# M5_Access_Switch_Dual_Input.net
KiCad netlist of a schematic drawn in EAGLE
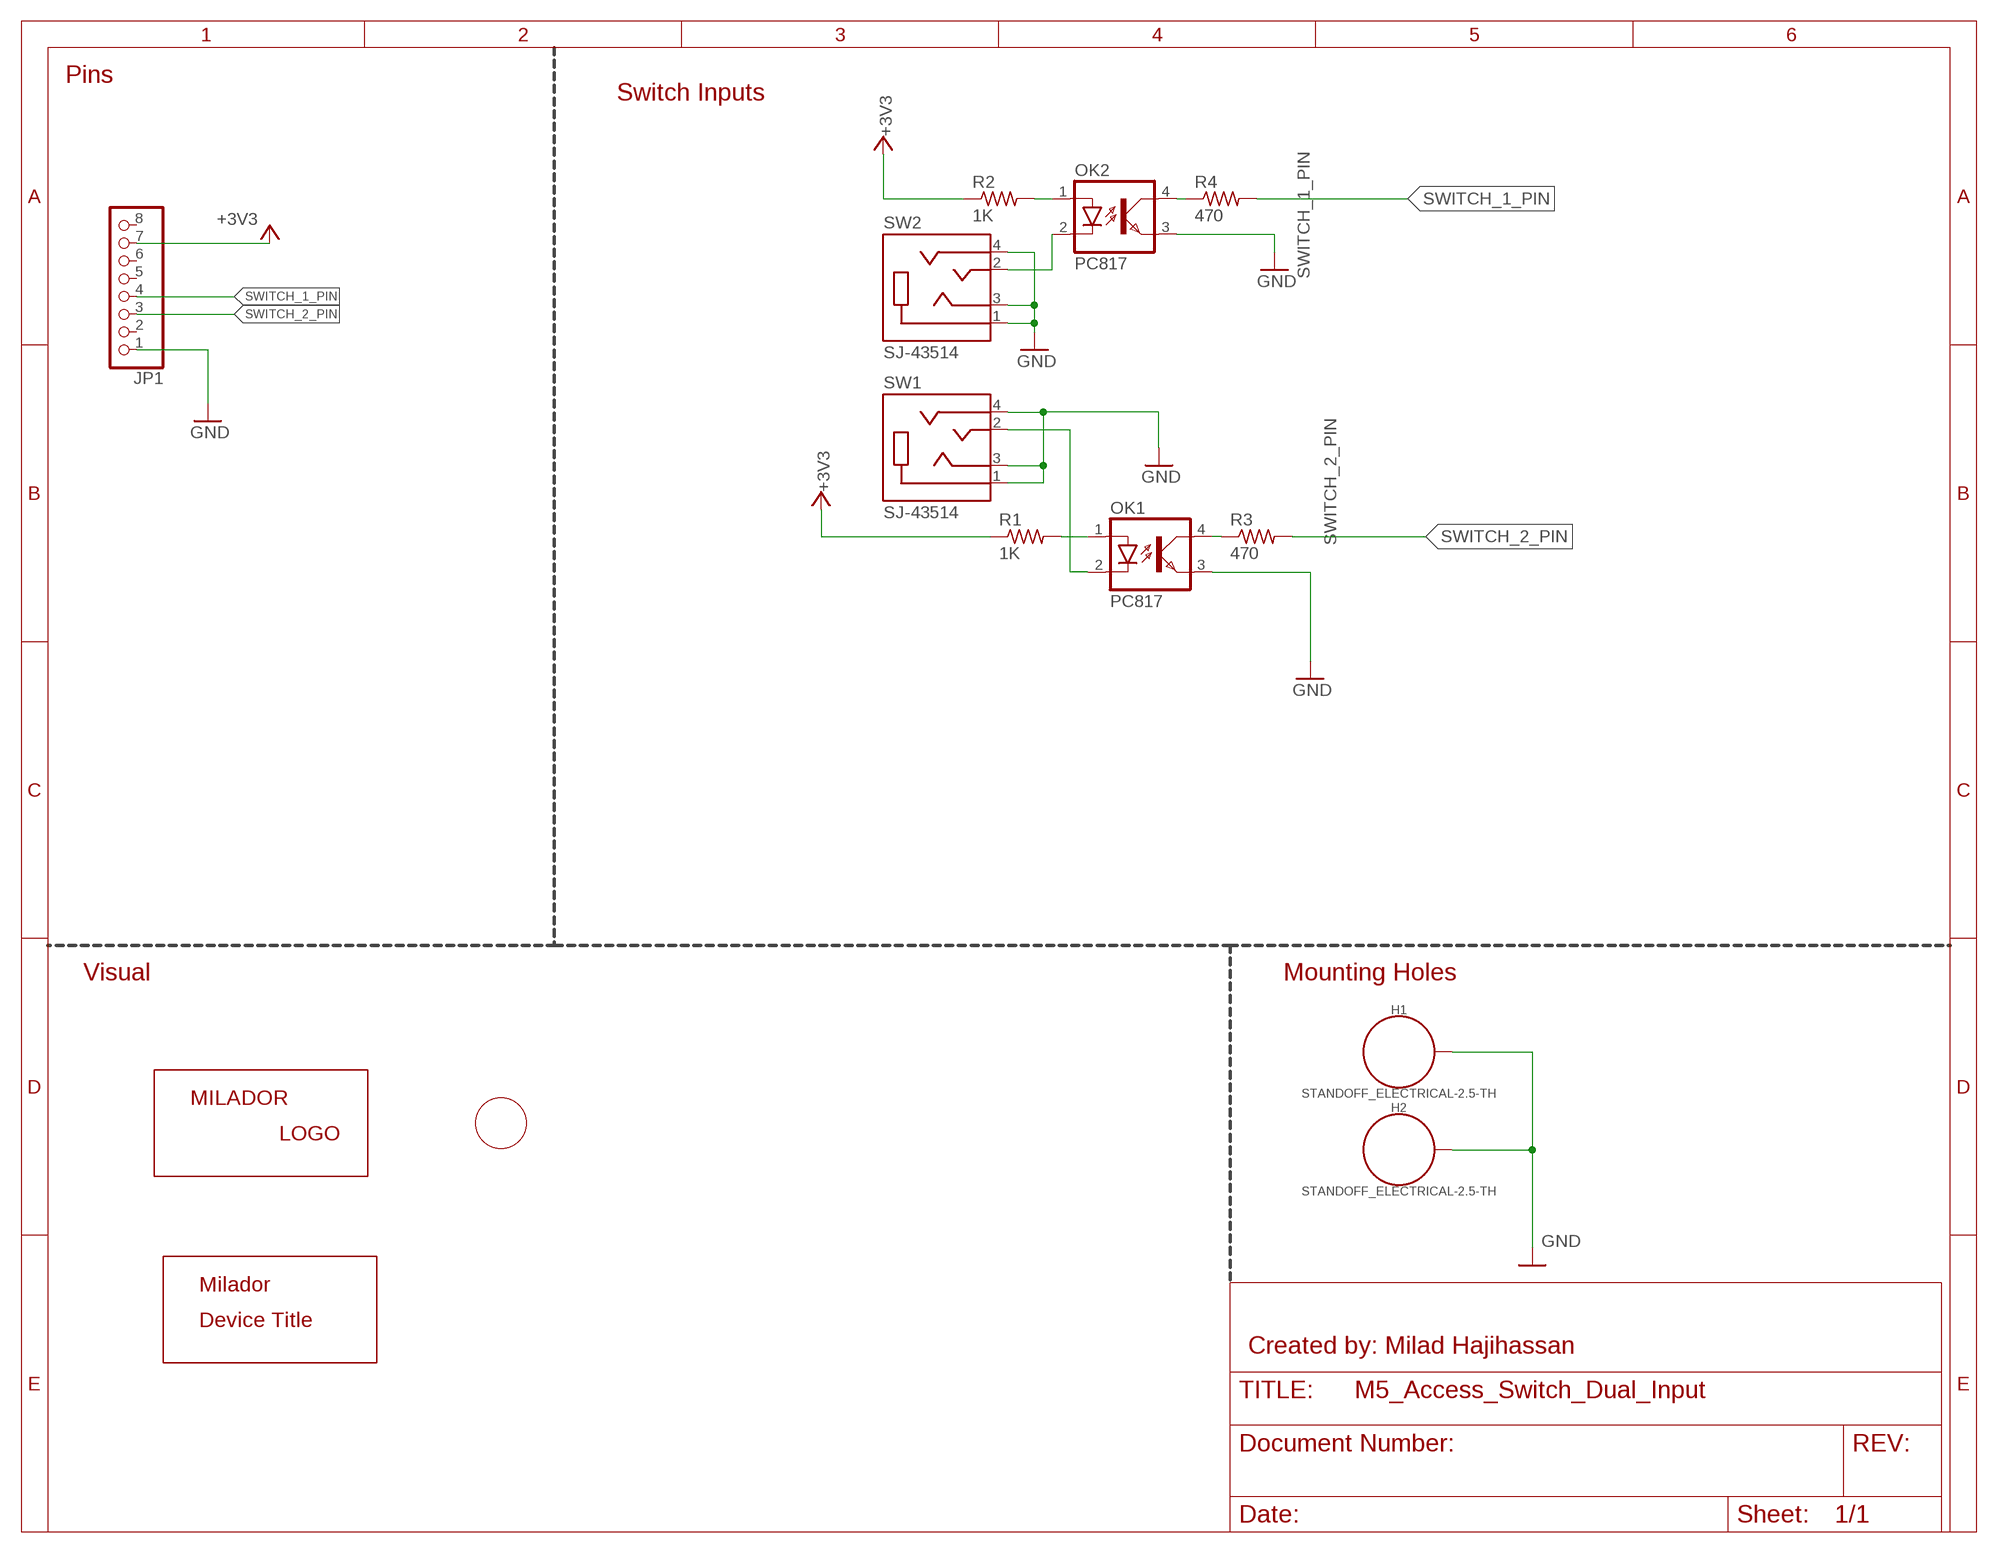
[diagram p0: schematic, sheet 1]

(export (version "E")
  (design (tool "Eeschema 10.0.6"))
  (components
    (comp (ref "H1")
      (value "STANDOFF_ELECTRICAL-2.5-TH")
      (footprint "eagle-import:STANDOFF-ELECTRICAL-2.5-TH")
      (libsource (lib "eagle-import") (part "STANDOFF_ELECTRICAL-2.5-TH"))
    )
    (comp (ref "H2")
      (value "STANDOFF_ELECTRICAL-2.5-TH")
      (footprint "eagle-import:STANDOFF-ELECTRICAL-2.5-TH")
      (libsource (lib "eagle-import") (part "STANDOFF_ELECTRICAL-2.5-TH"))
    )
    (comp (ref "JP1")
      (value "HEADER_MALE-1X8ROUND-RA")
      (footprint "eagle-import:1X08_ROUND_RA")
      (libsource (lib "eagle-import") (part "HEADER_MALE-1X8ROUND-RA"))
    )
    (comp (ref "LABEL_DEVICE_TOP")
      (value "MILADOR-DEVICE-M5-ACCESS-SWITCH")
      (footprint "eagle-import:MILADOR_M5_ACCESS_SWITCH")
      (libsource (lib "eagle-import") (part "MILADOR-DEVICE-M5-ACCESS-SWITCH"))
    )
    (comp (ref "LABEL_INPUT_TOP")
      (value "MILADOR-SWITCH-NAME-SW-INPUT")
      (footprint "eagle-import:SWITCH-INPUT")
      (libsource (lib "eagle-import") (part "MILADOR-SWITCH-NAME-SW-INPUT"))
    )
    (comp (ref "LABEL_LOGO_TOP")
      (value "MILADOR-LOGO-SM")
      (footprint "eagle-import:MILADOR_LOGO2")
      (libsource (lib "eagle-import") (part "MILADOR-LOGO-SM"))
    )
    (comp (ref "OK1")
      (value "PC817")
      (footprint "eagle-import:DIL04")
      (libsource (lib "eagle-import") (part "PC817"))
    )
    (comp (ref "OK2")
      (value "PC817")
      (footprint "eagle-import:DIL04")
      (libsource (lib "eagle-import") (part "PC817"))
    )
    (comp (ref "R1")
      (value "1K")
      (footprint "eagle-import:RESISTOR_0204_5")
      (libsource (lib "eagle-import") (part "RESISTOR-US-0204/5"))
    )
    (comp (ref "R2")
      (value "1K")
      (footprint "eagle-import:RESISTOR_0204_5")
      (libsource (lib "eagle-import") (part "RESISTOR-US-0204/5"))
    )
    (comp (ref "R3")
      (value "470")
      (footprint "eagle-import:RESISTOR_0204_5")
      (libsource (lib "eagle-import") (part "RESISTOR-US-0204/5"))
    )
    (comp (ref "R4")
      (value "470")
      (footprint "eagle-import:RESISTOR_0204_5")
      (libsource (lib "eagle-import") (part "RESISTOR-US-0204/5"))
    )
    (comp (ref "SW1")
      (value "SJ-43514")
      (footprint "eagle-import:CUI_SJ-43514")
      (libsource (lib "eagle-import") (part "SJ-43514"))
    )
    (comp (ref "SW2")
      (value "SJ-43514")
      (footprint "eagle-import:CUI_SJ-43514")
      (libsource (lib "eagle-import") (part "SJ-43514"))
    )
  )
  (nets
    (net (code "1") (name "+3V3") (class "Default")
      (node (ref "JP1") (pin "7") (pinfunction "7_7") (pintype "passive"))
      (node (ref "R1") (pin "1") (pinfunction "1_1") (pintype "passive"))
      (node (ref "R2") (pin "1") (pinfunction "1_1") (pintype "passive"))
    )
    (net (code "2") (name "GND") (class "Default")
      (node (ref "H1") (pin "P1") (pinfunction "P$1_P1") (pintype "bidirectional"))
      (node (ref "H2") (pin "P1") (pinfunction "P$1_P1") (pintype "bidirectional"))
      (node (ref "JP1") (pin "1") (pinfunction "1_1") (pintype "passive"))
      (node (ref "OK1") (pin "3") (pinfunction "EMIT_3") (pintype "passive"))
      (node (ref "OK2") (pin "3") (pinfunction "EMIT_3") (pintype "passive"))
      (node (ref "SW1") (pin "1") (pinfunction "SLEEVE_1") (pintype "passive"))
      (node (ref "SW1") (pin "3") (pinfunction "RING1_3") (pintype "passive"))
      (node (ref "SW1") (pin "4") (pinfunction "RING2_4") (pintype "passive"))
      (node (ref "SW2") (pin "1") (pinfunction "SLEEVE_1") (pintype "passive"))
      (node (ref "SW2") (pin "3") (pinfunction "RING1_3") (pintype "passive"))
      (node (ref "SW2") (pin "4") (pinfunction "RING2_4") (pintype "passive"))
    )
    (net (code "3") (name "Net-(OK1-A)") (class "Default")
      (node (ref "OK1") (pin "1") (pinfunction "A_1") (pintype "passive"))
      (node (ref "R1") (pin "2") (pinfunction "2_2") (pintype "passive"))
    )
    (net (code "4") (name "Net-(OK1-C)") (class "Default")
      (node (ref "OK1") (pin "2") (pinfunction "C_2") (pintype "passive"))
      (node (ref "SW1") (pin "2") (pinfunction "TIP_2") (pintype "passive"))
    )
    (net (code "5") (name "Net-(OK1-COL)") (class "Default")
      (node (ref "OK1") (pin "4") (pinfunction "COL_4") (pintype "passive"))
      (node (ref "R3") (pin "1") (pinfunction "1_1") (pintype "passive"))
    )
    (net (code "6") (name "Net-(OK2-A)") (class "Default")
      (node (ref "OK2") (pin "1") (pinfunction "A_1") (pintype "passive"))
      (node (ref "R2") (pin "2") (pinfunction "2_2") (pintype "passive"))
    )
    (net (code "7") (name "Net-(OK2-C)") (class "Default")
      (node (ref "OK2") (pin "2") (pinfunction "C_2") (pintype "passive"))
      (node (ref "SW2") (pin "2") (pinfunction "TIP_2") (pintype "passive"))
    )
    (net (code "8") (name "Net-(OK2-COL)") (class "Default")
      (node (ref "OK2") (pin "4") (pinfunction "COL_4") (pintype "passive"))
      (node (ref "R4") (pin "1") (pinfunction "1_1") (pintype "passive"))
    )
    (net (code "9") (name "SWITCH_1_PIN") (class "Default")
      (node (ref "JP1") (pin "4") (pinfunction "4_4") (pintype "passive"))
      (node (ref "R4") (pin "2") (pinfunction "2_2") (pintype "passive"))
    )
    (net (code "10") (name "SWITCH_2_PIN") (class "Default")
      (node (ref "JP1") (pin "3") (pinfunction "3_3") (pintype "passive"))
      (node (ref "R3") (pin "2") (pinfunction "2_2") (pintype "passive"))
    )
    (net (code "11") (name "unconnected-(JP1-Pad2)") (class "Default")
      (node (ref "JP1") (pin "2") (pinfunction "2_2") (pintype "passive"))
    )
    (net (code "12") (name "unconnected-(JP1-Pad5)") (class "Default")
      (node (ref "JP1") (pin "5") (pinfunction "5_5") (pintype "passive"))
    )
    (net (code "13") (name "unconnected-(JP1-Pad6)") (class "Default")
      (node (ref "JP1") (pin "6") (pinfunction "6_6") (pintype "passive"))
    )
    (net (code "14") (name "unconnected-(JP1-Pad8)") (class "Default")
      (node (ref "JP1") (pin "8") (pinfunction "8_8") (pintype "passive"))
    )
  )
)
